# PMU.net
KiCad netlist of a schematic drawn in Altium Designer
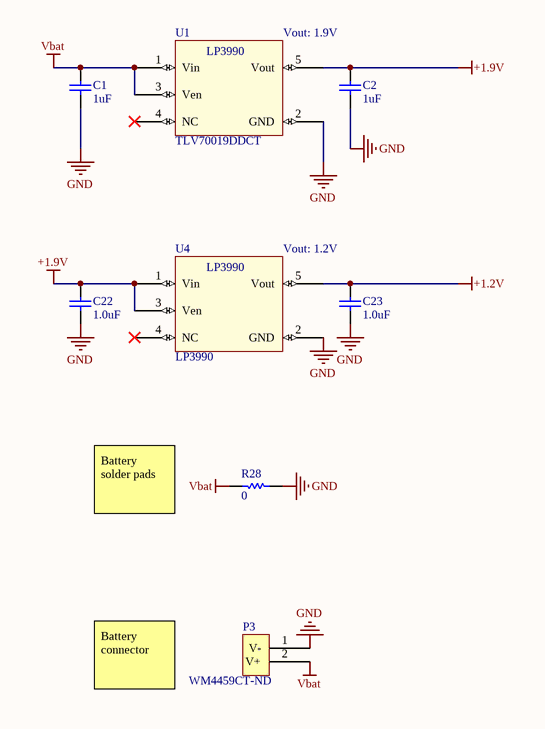
[diagram p0: PMU.SchDoc]

(export (version "E")
  (design (tool "Eeschema 10.0.6"))
  (components
    (comp (ref "C1")
      (value "1uF")
      (footprint "0402")
      (description "Capacitor (Semiconductor SIM Model)")
      (fields (field (name "PUBLISHER") "Altium Limited"))
      (libsource (lib "Miscellaneous Devices") (part "Cap Semi"))
    )
    (comp (ref "C2")
      (value "1uF")
      (footprint "0402")
      (description "Capacitor (Semiconductor SIM Model)")
      (fields (field (name "PUBLISHER") "Altium Limited"))
      (libsource (lib "Miscellaneous Devices") (part "Cap Semi"))
    )
    (comp (ref "C22")
      (value "1.0uF")
      (footprint "0201_Custom")
      (description "Capacitor (Semiconductor SIM Model)")
      (fields (field (name "PUBLISHER") "Altium Limited"))
      (libsource (lib "Miscellaneous Devices") (part "Cap Semi"))
    )
    (comp (ref "C23")
      (value "1.0uF")
      (footprint "0201_Custom")
      (description "Capacitor (Semiconductor SIM Model)")
      (fields (field (name "PUBLISHER") "Altium Limited"))
      (libsource (lib "Miscellaneous Devices") (part "Cap Semi"))
    )
    (comp (ref "P3")
      (value "WM4459CT-ND")
      (footprint "WM4459CT-ND_Footprint")
      (description "1.20MM WTB RECEPT CONNECTOR")
      (libsource (lib "headstage_parts") (part "WM4459CT-ND"))
    )
    (comp (ref "R28")
      (value "0")
      (footprint "1608[0603]")
      (description "Semiconductor Resistor")
      (fields (field (name "PUBLISHER") "Altium Limited"))
      (libsource (lib "Miscellaneous Devices") (part "Res Semi"))
    )
    (comp (ref "U1")
      (value "TLV70019DDCT")
      (footprint "SOT23-5Metric")
      (description "150mA Linear Voltage Regulator for Digital Applications")
      (fields (field (name "VOUT") "1.9V"))
      (libsource (lib "headstage_parts") (part "LP3990"))
    )
    (comp (ref "U4")
      (value "LP3990")
      (footprint "SOT23-5Metric")
      (description "150mA Linear Voltage Regulator for Digital Applications")
      (fields (field (name "VOUT") "1.2V"))
      (libsource (lib "headstage_parts") (part "LP3990"))
    )
  )
  (nets
    (net (code "1") (name "+1.2V") (class "Default")
      (node (ref "C23") (pin "1") (pinfunction "1_1") (pintype "passive"))
      (node (ref "U4") (pin "5") (pinfunction "Vout_5") (pintype "bidirectional"))
    )
    (net (code "2") (name "+1.9V") (class "Default")
      (node (ref "C2") (pin "2") (pinfunction "2_2") (pintype "passive"))
      (node (ref "C22") (pin "1") (pinfunction "1_1") (pintype "passive"))
      (node (ref "U1") (pin "5") (pinfunction "Vout_5") (pintype "bidirectional"))
      (node (ref "U4") (pin "1") (pinfunction "Vin_1") (pintype "bidirectional"))
      (node (ref "U4") (pin "3") (pinfunction "Ven_3") (pintype "bidirectional"))
    )
    (net (code "3") (name "GND") (class "Default")
      (node (ref "C1") (pin "1") (pinfunction "1_1") (pintype "passive"))
      (node (ref "C2") (pin "1") (pinfunction "1_1") (pintype "passive"))
      (node (ref "C22") (pin "2") (pinfunction "2_2") (pintype "passive"))
      (node (ref "C23") (pin "2") (pinfunction "2_2") (pintype "passive"))
      (node (ref "P3") (pin "1") (pinfunction "V-_1") (pintype "passive"))
      (node (ref "R28") (pin "1") (pinfunction "1_1") (pintype "passive"))
      (node (ref "U1") (pin "2") (pinfunction "GND_2") (pintype "bidirectional"))
      (node (ref "U4") (pin "2") (pinfunction "GND_2") (pintype "bidirectional"))
    )
    (net (code "4") (name "Vbat") (class "Default")
      (node (ref "C1") (pin "2") (pinfunction "2_2") (pintype "passive"))
      (node (ref "P3") (pin "2") (pinfunction "V+_2") (pintype "passive"))
      (node (ref "R28") (pin "2") (pinfunction "2_2") (pintype "passive"))
      (node (ref "U1") (pin "1") (pinfunction "Vin_1") (pintype "bidirectional"))
      (node (ref "U1") (pin "3") (pinfunction "Ven_3") (pintype "bidirectional"))
    )
    (net (code "5") (name "unconnected-(U1-NC-Pad4)") (class "Default")
      (node (ref "U1") (pin "4") (pinfunction "NC_4") (pintype "bidirectional+no_connect"))
    )
    (net (code "6") (name "unconnected-(U4-NC-Pad4)") (class "Default")
      (node (ref "U4") (pin "4") (pinfunction "NC_4") (pintype "bidirectional+no_connect"))
    )
  )
)
